# ThermocoupleFrontEnd.net
KiCad netlist of a schematic drawn in Altium Designer
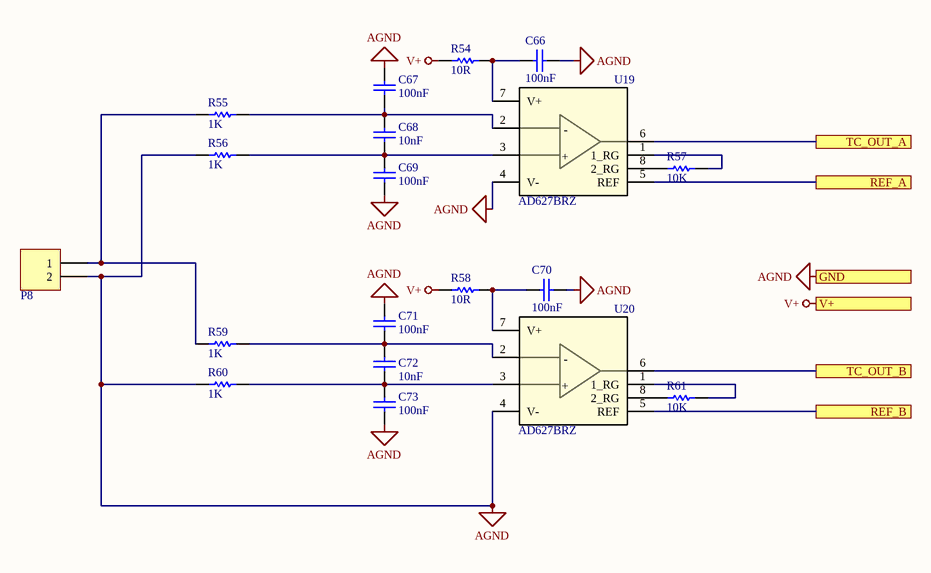
[diagram p0: ThermocoupleFrontEnd.SchDoc]

(export (version "E")
  (design (tool "Eeschema 10.0.6"))
  (components
    (comp (ref "C66")
      (value "100nF")
      (footprint "R0603_C")
      (description "精度 ±10% \r\n容值 100nF \r\n额定电压 50V \r\n温漂系数（介质材料) X7R")
      (libsource (lib "00Lib") (part "100nF/0603/50V"))
    )
    (comp (ref "C67")
      (value "100nF")
      (footprint "R0603_C")
      (description "精度 ±10% \r\n容值 100nF \r\n额定电压 50V \r\n温漂系数（介质材料) X7R")
      (libsource (lib "00Lib") (part "100nF/0603/50V"))
    )
    (comp (ref "C68")
      (value "10nF")
      (footprint "R0603_C")
      (description "精度 ±5% \r\n容值 10nF \r\n额定电压 50V \r\n温漂系数（介质材料) C0G")
      (libsource (lib "00Lib") (part "10nF/0603/C0G/50V"))
    )
    (comp (ref "C69")
      (value "100nF")
      (footprint "R0603_C")
      (description "精度 ±10% \r\n容值 100nF \r\n额定电压 50V \r\n温漂系数（介质材料) X7R")
      (libsource (lib "00Lib") (part "100nF/0603/50V"))
    )
    (comp (ref "C70")
      (value "100nF")
      (footprint "R0603_C")
      (description "精度 ±10% \r\n容值 100nF \r\n额定电压 50V \r\n温漂系数（介质材料) X7R")
      (libsource (lib "00Lib") (part "100nF/0603/50V"))
    )
    (comp (ref "C71")
      (value "100nF")
      (footprint "R0603_C")
      (description "精度 ±10% \r\n容值 100nF \r\n额定电压 50V \r\n温漂系数（介质材料) X7R")
      (libsource (lib "00Lib") (part "100nF/0603/50V"))
    )
    (comp (ref "C72")
      (value "10nF")
      (footprint "R0603_C")
      (description "精度 ±5% \r\n容值 10nF \r\n额定电压 50V \r\n温漂系数（介质材料) C0G")
      (libsource (lib "00Lib") (part "10nF/0603/C0G/50V"))
    )
    (comp (ref "C73")
      (value "100nF")
      (footprint "R0603_C")
      (description "精度 ±10% \r\n容值 100nF \r\n额定电压 50V \r\n温漂系数（介质材料) X7R")
      (libsource (lib "00Lib") (part "100nF/0603/50V"))
    )
    (comp (ref "P8")
      (value "Header 2")
      (footprint "CP1X2")
      (description "Header, 2-Pin")
      (libsource (lib "00Lib") (part "Header 2"))
    )
    (comp (ref "R54")
      (value "10R")
      (footprint "R0603_R")
      (description "精度 ±1% \r\n阻值 10Ω \r\n温度系数 ±100ppm/℃ \r\n功率 0.1W")
      (libsource (lib "00Lib") (part "10R/0603"))
    )
    (comp (ref "R55")
      (value "1K")
      (footprint "R0603_R")
      (description "精度 ±1% \r\n温度系数 ±100ppm/℃ \r\n阻值 1kΩ \r\n功率 0.1W")
      (libsource (lib "00Lib") (part "1K/0603"))
    )
    (comp (ref "R56")
      (value "1K")
      (footprint "R0603_R")
      (description "精度 ±1% \r\n温度系数 ±100ppm/℃ \r\n阻值 1kΩ \r\n功率 0.1W")
      (libsource (lib "00Lib") (part "1K/0603"))
    )
    (comp (ref "R57")
      (value "10K")
      (footprint "R0603_R")
      (description "精度 ±1% \r\n温度系数 ±100ppm/℃ \r\n阻值 10kΩ \r\n功率 0.1W")
      (libsource (lib "00Lib") (part "10K/0603"))
    )
    (comp (ref "R58")
      (value "10R")
      (footprint "R0603_R")
      (description "精度 ±1% \r\n阻值 10Ω \r\n温度系数 ±100ppm/℃ \r\n功率 0.1W")
      (libsource (lib "00Lib") (part "10R/0603"))
    )
    (comp (ref "R59")
      (value "1K")
      (footprint "R0603_R")
      (description "精度 ±1% \r\n温度系数 ±100ppm/℃ \r\n阻值 1kΩ \r\n功率 0.1W")
      (libsource (lib "00Lib") (part "1K/0603"))
    )
    (comp (ref "R60")
      (value "1K")
      (footprint "R0603_R")
      (description "精度 ±1% \r\n温度系数 ±100ppm/℃ \r\n阻值 1kΩ \r\n功率 0.1W")
      (libsource (lib "00Lib") (part "1K/0603"))
    )
    (comp (ref "R61")
      (value "10K")
      (footprint "R0603_R")
      (description "精度 ±1% \r\n温度系数 ±100ppm/℃ \r\n阻值 10kΩ \r\n功率 0.1W")
      (libsource (lib "00Lib") (part "10K/0603"))
    )
    (comp (ref "U19")
      (value "AD627BRZ")
      (footprint "SOP-8_150mil")
      (libsource (lib "00Lib") (part "AD627BRZ"))
    )
    (comp (ref "U20")
      (value "AD627BRZ")
      (footprint "SOP-8_150mil")
      (libsource (lib "00Lib") (part "AD627BRZ"))
    )
  )
  (nets
    (net (code "1") (name "/REF_A") (class "Default")
      (node (ref "U19") (pin "5") (pinfunction "REF_5") (pintype "passive"))
    )
    (net (code "2") (name "/REF_B") (class "Default")
      (node (ref "U20") (pin "5") (pinfunction "REF_5") (pintype "passive"))
    )
    (net (code "3") (name "/TC_OUT_A") (class "Default")
      (node (ref "U19") (pin "6") (pinfunction "VOUT_6") (pintype "passive"))
    )
    (net (code "4") (name "/TC_OUT_B") (class "Default")
      (node (ref "U20") (pin "6") (pinfunction "VOUT_6") (pintype "passive"))
    )
    (net (code "5") (name "AGND") (class "Default")
      (node (ref "C66") (pin "1") (pinfunction "1_1") (pintype "passive"))
      (node (ref "C67") (pin "1") (pinfunction "1_1") (pintype "passive"))
      (node (ref "C69") (pin "2") (pinfunction "2_2") (pintype "passive"))
      (node (ref "C70") (pin "1") (pinfunction "1_1") (pintype "passive"))
      (node (ref "C71") (pin "1") (pinfunction "1_1") (pintype "passive"))
      (node (ref "C73") (pin "2") (pinfunction "2_2") (pintype "passive"))
      (node (ref "P8") (pin "2") (pinfunction "2_2") (pintype "passive"))
      (node (ref "R56") (pin "1") (pinfunction "1_1") (pintype "passive"))
      (node (ref "R60") (pin "1") (pinfunction "1_1") (pintype "passive"))
      (node (ref "U19") (pin "4") (pinfunction "V-_4") (pintype "power_in"))
      (node (ref "U20") (pin "4") (pinfunction "V-_4") (pintype "power_in"))
    )
    (net (code "6") (name "Net-(P8-Pad1)") (class "Default")
      (node (ref "P8") (pin "1") (pinfunction "1_1") (pintype "passive"))
      (node (ref "R55") (pin "1") (pinfunction "1_1") (pintype "passive"))
      (node (ref "R59") (pin "1") (pinfunction "1_1") (pintype "passive"))
    )
    (net (code "7") (name "Net-(U19-1_RG)") (class "Default")
      (node (ref "R57") (pin "1") (pinfunction "1_1") (pintype "passive"))
      (node (ref "U19") (pin "1") (pinfunction "1_RG_1") (pintype "passive"))
    )
    (net (code "8") (name "Net-(U19-2_RG)") (class "Default")
      (node (ref "R57") (pin "2") (pinfunction "2_2") (pintype "passive"))
      (node (ref "U19") (pin "8") (pinfunction "2_RG_8") (pintype "passive"))
    )
    (net (code "9") (name "Net-(U19-V+)") (class "Default")
      (node (ref "C66") (pin "2") (pinfunction "2_2") (pintype "passive"))
      (node (ref "R54") (pin "1") (pinfunction "1_1") (pintype "passive"))
      (node (ref "U19") (pin "7") (pinfunction "V+_7") (pintype "power_in"))
    )
    (net (code "10") (name "Net-(U19-VIN+)") (class "Default")
      (node (ref "C68") (pin "2") (pinfunction "2_2") (pintype "passive"))
      (node (ref "C69") (pin "1") (pinfunction "1_1") (pintype "passive"))
      (node (ref "R56") (pin "2") (pinfunction "2_2") (pintype "passive"))
      (node (ref "U19") (pin "3") (pinfunction "VIN+_3") (pintype "tri_state"))
    )
    (net (code "11") (name "Net-(U19-VIN-)") (class "Default")
      (node (ref "C67") (pin "2") (pinfunction "2_2") (pintype "passive"))
      (node (ref "C68") (pin "1") (pinfunction "1_1") (pintype "passive"))
      (node (ref "R55") (pin "2") (pinfunction "2_2") (pintype "passive"))
      (node (ref "U19") (pin "2") (pinfunction "VIN-_2") (pintype "tri_state"))
    )
    (net (code "12") (name "Net-(U20-1_RG)") (class "Default")
      (node (ref "R61") (pin "1") (pinfunction "1_1") (pintype "passive"))
      (node (ref "U20") (pin "1") (pinfunction "1_RG_1") (pintype "passive"))
    )
    (net (code "13") (name "Net-(U20-2_RG)") (class "Default")
      (node (ref "R61") (pin "2") (pinfunction "2_2") (pintype "passive"))
      (node (ref "U20") (pin "8") (pinfunction "2_RG_8") (pintype "passive"))
    )
    (net (code "14") (name "Net-(U20-V+)") (class "Default")
      (node (ref "C70") (pin "2") (pinfunction "2_2") (pintype "passive"))
      (node (ref "R58") (pin "1") (pinfunction "1_1") (pintype "passive"))
      (node (ref "U20") (pin "7") (pinfunction "V+_7") (pintype "power_in"))
    )
    (net (code "15") (name "Net-(U20-VIN+)") (class "Default")
      (node (ref "C72") (pin "2") (pinfunction "2_2") (pintype "passive"))
      (node (ref "C73") (pin "1") (pinfunction "1_1") (pintype "passive"))
      (node (ref "R60") (pin "2") (pinfunction "2_2") (pintype "passive"))
      (node (ref "U20") (pin "3") (pinfunction "VIN+_3") (pintype "tri_state"))
    )
    (net (code "16") (name "Net-(U20-VIN-)") (class "Default")
      (node (ref "C71") (pin "2") (pinfunction "2_2") (pintype "passive"))
      (node (ref "C72") (pin "1") (pinfunction "1_1") (pintype "passive"))
      (node (ref "R59") (pin "2") (pinfunction "2_2") (pintype "passive"))
      (node (ref "U20") (pin "2") (pinfunction "VIN-_2") (pintype "tri_state"))
    )
    (net (code "17") (name "V+") (class "Default")
      (node (ref "R54") (pin "2") (pinfunction "2_2") (pintype "passive"))
      (node (ref "R58") (pin "2") (pinfunction "2_2") (pintype "passive"))
    )
  )
)
